# communication_shield.net
KiCad netlist of a schematic drawn in EAGLE
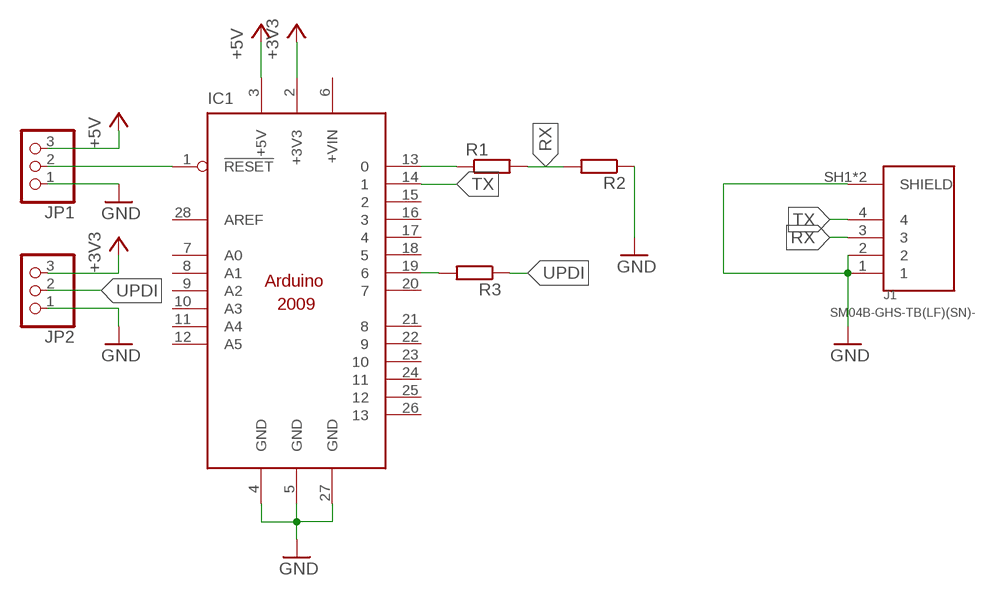
[diagram p0: schematic, sheet 1]

(export (version "E")
  (design (tool "Eeschema 10.0.6"))
  (components
    (comp (ref "IC1")
      (value "ARDUINO2009_10")
      (footprint "eagle-import:ARDUINO2009")
      (libsource (lib "eagle-import") (part "ARDUINO2009_10"))
    )
    (comp (ref "J1")
      (value "SM04B-GHS-TB(LF)(SN)-")
      (footprint "eagle-import:JST_SM04B-GHS-TB(LF)(SN)-")
      (fields (field (name "DIGI-KEY_PART_NUMBER") "455-1566-6-ND") (field (name "MF") "JST Sales"))
      (libsource (lib "eagle-import") (part "SM04B-GHS-TB(LF)(SN)-"))
    )
    (comp (ref "JP1")
      (value "PINHD-1X3")
      (footprint "eagle-import:1X03")
      (libsource (lib "eagle-import") (part "PINHD-1X3"))
    )
    (comp (ref "JP2")
      (value "PINHD-1X3")
      (footprint "eagle-import:1X03")
      (libsource (lib "eagle-import") (part "PINHD-1X3"))
    )
    (comp (ref "R1")
      (value "R-EU_0204/7")
      (footprint "eagle-import:0204_7")
      (libsource (lib "eagle-import") (part "R-EU_0204/7"))
    )
    (comp (ref "R2")
      (value "R-EU_0204/7")
      (footprint "eagle-import:0204_7")
      (libsource (lib "eagle-import") (part "R-EU_0204/7"))
    )
    (comp (ref "R3")
      (value "R-EU_0204/7")
      (footprint "eagle-import:0204_7")
      (libsource (lib "eagle-import") (part "R-EU_0204/7"))
    )
  )
  (nets
    (net (code "1") (name "+3V3") (class "Default")
      (node (ref "IC1") (pin "2") (pinfunction "+3V3_2") (pintype "power_in"))
      (node (ref "JP2") (pin "3") (pinfunction "3_3") (pintype "passive"))
    )
    (net (code "2") (name "+5V") (class "Default")
      (node (ref "IC1") (pin "3") (pinfunction "+5V_3") (pintype "power_in"))
      (node (ref "JP1") (pin "3") (pinfunction "3_3") (pintype "passive"))
    )
    (net (code "3") (name "GND") (class "Default")
      (node (ref "IC1") (pin "27") (pinfunction "GND_27") (pintype "power_in"))
      (node (ref "IC1") (pin "4") (pinfunction "GND_4") (pintype "power_in"))
      (node (ref "IC1") (pin "5") (pinfunction "GND_5") (pintype "power_in"))
      (node (ref "J1") (pin "1") (pinfunction "1_1") (pintype "passive"))
      (node (ref "J1") (pin "2") (pinfunction "2_2") (pintype "passive"))
      (node (ref "J1") (pin "SH1") (pinfunction "SHIELD_SH1") (pintype "power_in"))
      (node (ref "J1") (pin "SH2") (pinfunction "SHIELD_SH2") (pintype "power_in"))
      (node (ref "JP1") (pin "1") (pinfunction "1_1") (pintype "passive"))
      (node (ref "JP2") (pin "1") (pinfunction "1_1") (pintype "passive"))
      (node (ref "R2") (pin "1") (pinfunction "1_1") (pintype "passive"))
    )
    (net (code "4") (name "Net-(IC1-0)") (class "Default")
      (node (ref "IC1") (pin "13") (pinfunction "0_13") (pintype "bidirectional"))
      (node (ref "R1") (pin "1") (pinfunction "1_1") (pintype "passive"))
    )
    (net (code "5") (name "Net-(IC1-6)") (class "Default")
      (node (ref "IC1") (pin "19") (pinfunction "6_19") (pintype "bidirectional"))
      (node (ref "R3") (pin "2") (pinfunction "2_2") (pintype "passive"))
    )
    (net (code "6") (name "Net-(IC1-~{RESET})") (class "Default")
      (node (ref "IC1") (pin "1") (pinfunction "~{RESET}_1") (pintype "bidirectional"))
      (node (ref "JP1") (pin "2") (pinfunction "2_2") (pintype "passive"))
    )
    (net (code "7") (name "RX") (class "Default")
      (node (ref "J1") (pin "3") (pinfunction "3_3") (pintype "passive"))
      (node (ref "R1") (pin "2") (pinfunction "2_2") (pintype "passive"))
      (node (ref "R2") (pin "2") (pinfunction "2_2") (pintype "passive"))
    )
    (net (code "8") (name "TX") (class "Default")
      (node (ref "IC1") (pin "14") (pinfunction "1_14") (pintype "bidirectional"))
      (node (ref "J1") (pin "4") (pinfunction "4_4") (pintype "passive"))
    )
    (net (code "9") (name "UPDI") (class "Default")
      (node (ref "JP2") (pin "2") (pinfunction "2_2") (pintype "passive"))
      (node (ref "R3") (pin "1") (pinfunction "1_1") (pintype "passive"))
    )
    (net (code "10") (name "unconnected-(IC1-+VIN-Pad6)") (class "Default")
      (node (ref "IC1") (pin "6") (pinfunction "+VIN_6") (pintype "bidirectional"))
    )
    (net (code "11") (name "unconnected-(IC1-2-Pad15)") (class "Default")
      (node (ref "IC1") (pin "15") (pinfunction "2_15") (pintype "bidirectional"))
    )
    (net (code "12") (name "unconnected-(IC1-3-Pad16)") (class "Default")
      (node (ref "IC1") (pin "16") (pinfunction "3_16") (pintype "bidirectional"))
    )
    (net (code "13") (name "unconnected-(IC1-4-Pad17)") (class "Default")
      (node (ref "IC1") (pin "17") (pinfunction "4_17") (pintype "bidirectional"))
    )
    (net (code "14") (name "unconnected-(IC1-5-Pad18)") (class "Default")
      (node (ref "IC1") (pin "18") (pinfunction "5_18") (pintype "bidirectional"))
    )
    (net (code "15") (name "unconnected-(IC1-7-Pad20)") (class "Default")
      (node (ref "IC1") (pin "20") (pinfunction "7_20") (pintype "bidirectional"))
    )
    (net (code "16") (name "unconnected-(IC1-8-Pad21)") (class "Default")
      (node (ref "IC1") (pin "21") (pinfunction "8_21") (pintype "bidirectional"))
    )
    (net (code "17") (name "unconnected-(IC1-9-Pad22)") (class "Default")
      (node (ref "IC1") (pin "22") (pinfunction "9_22") (pintype "bidirectional"))
    )
    (net (code "18") (name "unconnected-(IC1-10-Pad23)") (class "Default")
      (node (ref "IC1") (pin "23") (pinfunction "10_23") (pintype "bidirectional"))
    )
    (net (code "19") (name "unconnected-(IC1-11-Pad24)") (class "Default")
      (node (ref "IC1") (pin "24") (pinfunction "11_24") (pintype "bidirectional"))
    )
    (net (code "20") (name "unconnected-(IC1-12-Pad25)") (class "Default")
      (node (ref "IC1") (pin "25") (pinfunction "12_25") (pintype "bidirectional"))
    )
    (net (code "21") (name "unconnected-(IC1-13-Pad26)") (class "Default")
      (node (ref "IC1") (pin "26") (pinfunction "13_26") (pintype "bidirectional"))
    )
    (net (code "22") (name "unconnected-(IC1-A0-Pad7)") (class "Default")
      (node (ref "IC1") (pin "7") (pinfunction "A0_7") (pintype "bidirectional"))
    )
    (net (code "23") (name "unconnected-(IC1-A1-Pad8)") (class "Default")
      (node (ref "IC1") (pin "8") (pinfunction "A1_8") (pintype "bidirectional"))
    )
    (net (code "24") (name "unconnected-(IC1-A2-Pad9)") (class "Default")
      (node (ref "IC1") (pin "9") (pinfunction "A2_9") (pintype "bidirectional"))
    )
    (net (code "25") (name "unconnected-(IC1-A3-Pad10)") (class "Default")
      (node (ref "IC1") (pin "10") (pinfunction "A3_10") (pintype "bidirectional"))
    )
    (net (code "26") (name "unconnected-(IC1-A4-Pad11)") (class "Default")
      (node (ref "IC1") (pin "11") (pinfunction "A4_11") (pintype "bidirectional"))
    )
    (net (code "27") (name "unconnected-(IC1-A5-Pad12)") (class "Default")
      (node (ref "IC1") (pin "12") (pinfunction "A5_12") (pintype "bidirectional"))
    )
    (net (code "28") (name "unconnected-(IC1-AREF-Pad28)") (class "Default")
      (node (ref "IC1") (pin "28") (pinfunction "AREF_28") (pintype "bidirectional"))
    )
  )
)
